# Schematic.net
KiCad netlist of a schematic drawn in Altium Designer
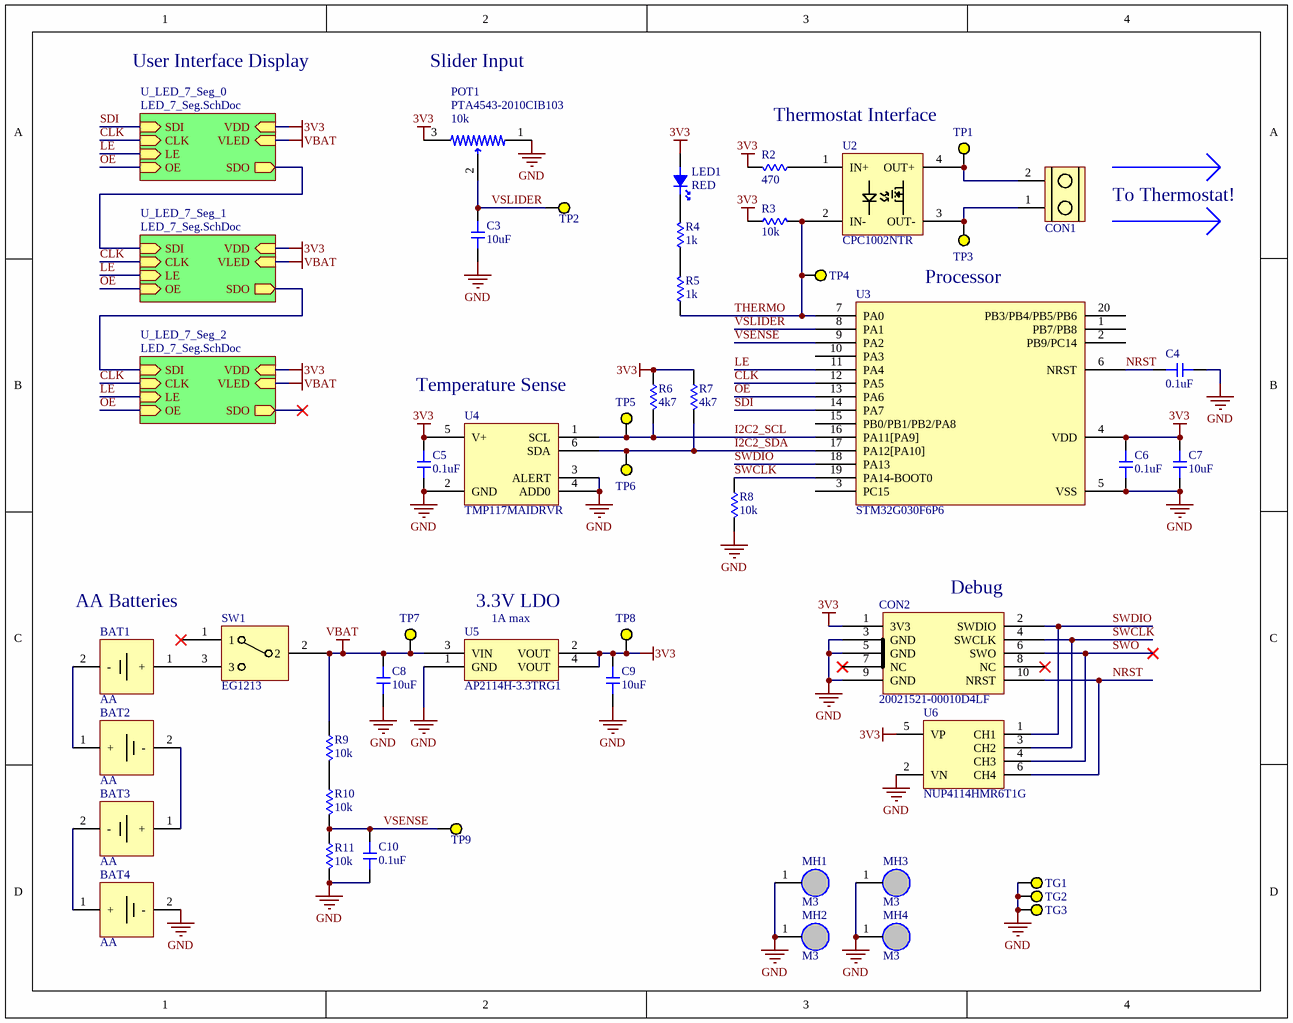
[diagram p0: Schematic.SchDoc]

(export (version "E")
  (design (tool "Eeschema 10.0.6"))
  (components
    (comp (ref "BAT1")
      (value "AA")
      (footprint "AA_BATTERY")
      (description "AA BATTERY")
      (libsource (lib "") (part "AA_BATTERY_1"))
    )
    (comp (ref "BAT2")
      (value "AA")
      (footprint "AA_BATTERY")
      (description "AA BATTERY")
      (libsource (lib "Schlib") (part "AA_BATTERY"))
    )
    (comp (ref "BAT3")
      (value "AA")
      (footprint "AA_BATTERY")
      (description "AA BATTERY")
      (libsource (lib "") (part "AA_BATTERY_1"))
    )
    (comp (ref "BAT4")
      (value "AA")
      (footprint "AA_BATTERY")
      (description "AA BATTERY")
      (libsource (lib "Schlib") (part "AA_BATTERY"))
    )
    (comp (ref "C3")
      (value "10uF")
      (footprint "PcbLib:0603-CAP")
      (description "Capacitor")
      (libsource (lib "AMDC") (part "Capacitor"))
    )
    (comp (ref "C4")
      (value "0.1uF")
      (footprint "PcbLib:0603-CAP")
      (description "Capacitor")
      (libsource (lib "AMDC") (part "Capacitor"))
    )
    (comp (ref "C5")
      (value "0.1uF")
      (footprint "PcbLib:0603-CAP")
      (description "Capacitor")
      (libsource (lib "AMDC") (part "Capacitor"))
    )
    (comp (ref "C6")
      (value "0.1uF")
      (footprint "PcbLib:0603-CAP")
      (description "Capacitor")
      (libsource (lib "AMDC") (part "Capacitor"))
    )
    (comp (ref "C7")
      (value "10uF")
      (footprint "PcbLib:0603-CAP")
      (description "Capacitor")
      (libsource (lib "AMDC") (part "Capacitor"))
    )
    (comp (ref "C8")
      (value "10uF")
      (footprint "PcbLib:0603-CAP")
      (description "Capacitor")
      (libsource (lib "AMDC") (part "Capacitor"))
    )
    (comp (ref "C9")
      (value "10uF")
      (footprint "PcbLib:0603-CAP")
      (description "Capacitor")
      (libsource (lib "AMDC") (part "Capacitor"))
    )
    (comp (ref "C10")
      (value "0.1uF")
      (footprint "PcbLib:0603-CAP")
      (description "Capacitor")
      (libsource (lib "AMDC") (part "Capacitor"))
    )
    (comp (ref "CON1")
      (value "ScrewTerminal_1x2")
      (footprint "AMDC:1935161")
      (libsource (lib "AMDC") (part "ScrewTerminal_1x2"))
    )
    (comp (ref "CON2")
      (value "20021521-00010D4LF")
      (footprint "SensorCard:20021521-00010D4LF")
      (description "CONN HEADER SMD 10POS 1.27MM")
      (libsource (lib "SensorMotherBoard") (part "20021521-00010D4LF"))
    )
    (comp (ref "LED1") (value "RED") (footprint "PcbLib:0603-LED") (libsource (lib "AMDC") (part "LED")))
    (comp (ref "MH1")
      (value "M3")
      (footprint "M3_HOLE")
      (description "M3 MOUNTING HOLE")
      (libsource (lib "Schlib") (part "M3_HOLE"))
    )
    (comp (ref "MH2")
      (value "M3")
      (footprint "M3_HOLE")
      (description "M3 MOUNTING HOLE")
      (libsource (lib "Schlib") (part "M3_HOLE"))
    )
    (comp (ref "MH3")
      (value "M3")
      (footprint "M3_HOLE")
      (description "M3 MOUNTING HOLE")
      (libsource (lib "Schlib") (part "M3_HOLE"))
    )
    (comp (ref "MH4")
      (value "M3")
      (footprint "M3_HOLE")
      (description "M3 MOUNTING HOLE")
      (libsource (lib "Schlib") (part "M3_HOLE"))
    )
    (comp (ref "POT1")
      (value "PTA4543-2010CIB103")
      (footprint "PTA4543-2010CIB103")
      (description "SLIDE POT 10K OHM 0.25W TOP 45MM")
      (fields (field (name "ALTIUM_VALUE") "10k"))
      (libsource (lib "Schlib") (part "PTA4543-2010CIB103"))
    )
    (comp (ref "R2")
      (value "470")
      (footprint "PcbLib:0603-RES")
      (fields (field (name "Comment") "Resistor"))
      (libsource (lib "*") (part "Resistor"))
    )
    (comp (ref "R3")
      (value "10k")
      (footprint "PcbLib:0603-RES")
      (fields (field (name "Comment") "Resistor"))
      (libsource (lib "*") (part "Resistor"))
    )
    (comp (ref "R4")
      (value "1k")
      (footprint "PcbLib:0603-RES")
      (fields (field (name "Comment") "Resistor"))
      (libsource (lib "*") (part "Resistor"))
    )
    (comp (ref "R5")
      (value "1k")
      (footprint "PcbLib:0603-RES")
      (fields (field (name "Comment") "Resistor"))
      (libsource (lib "*") (part "Resistor"))
    )
    (comp (ref "R6")
      (value "4k7")
      (footprint "PcbLib:0603-RES")
      (fields (field (name "Comment") "Resistor"))
      (libsource (lib "*") (part "Resistor"))
    )
    (comp (ref "R7")
      (value "4k7")
      (footprint "PcbLib:0603-RES")
      (fields (field (name "Comment") "Resistor"))
      (libsource (lib "*") (part "Resistor"))
    )
    (comp (ref "R8")
      (value "10k")
      (footprint "PcbLib:0603-RES")
      (fields (field (name "Comment") "Resistor"))
      (libsource (lib "*") (part "Resistor"))
    )
    (comp (ref "R9")
      (value "10k")
      (footprint "PcbLib:0603-RES")
      (fields (field (name "Comment") "Resistor"))
      (libsource (lib "*") (part "Resistor"))
    )
    (comp (ref "R10")
      (value "10k")
      (footprint "PcbLib:0603-RES")
      (fields (field (name "Comment") "Resistor"))
      (libsource (lib "*") (part "Resistor"))
    )
    (comp (ref "R11")
      (value "10k")
      (footprint "PcbLib:0603-RES")
      (fields (field (name "Comment") "Resistor"))
      (libsource (lib "*") (part "Resistor"))
    )
    (comp (ref "SW1")
      (value "EG1213")
      (footprint "EG1213")
      (description "SWITCH SLIDE SPDT 200MA 30V")
      (libsource (lib "Schlib") (part "EG1213"))
    )
    (comp (ref "TG1")
      (value "RCU-0C")
      (footprint "AMDC:RCU-0C")
      (description "PC TEST POINT NATURAL")
      (libsource (lib "Altium Content Vault") (part "KSTN-TP-5004"))
    )
    (comp (ref "TG2")
      (value "RCU-0C")
      (footprint "AMDC:RCU-0C")
      (description "PC TEST POINT NATURAL")
      (libsource (lib "Altium Content Vault") (part "KSTN-TP-5004"))
    )
    (comp (ref "TG3")
      (value "RCU-0C")
      (footprint "AMDC:RCU-0C")
      (description "PC TEST POINT NATURAL")
      (libsource (lib "Altium Content Vault") (part "KSTN-TP-5004"))
    )
    (comp (ref "TP1")
      (value "RCU-0C")
      (footprint "AMDC:RCU-0C")
      (description "PC TEST POINT NATURAL")
      (libsource (lib "Altium Content Vault") (part "KSTN-TP-5004"))
    )
    (comp (ref "TP2")
      (value "RCU-0C")
      (footprint "AMDC:RCU-0C")
      (description "PC TEST POINT NATURAL")
      (libsource (lib "Altium Content Vault") (part "KSTN-TP-5004"))
    )
    (comp (ref "TP3")
      (value "RCU-0C")
      (footprint "AMDC:RCU-0C")
      (description "PC TEST POINT NATURAL")
      (libsource (lib "Altium Content Vault") (part "KSTN-TP-5004"))
    )
    (comp (ref "TP4")
      (value "RCU-0C")
      (footprint "AMDC:RCU-0C")
      (description "PC TEST POINT NATURAL")
      (libsource (lib "Altium Content Vault") (part "KSTN-TP-5004"))
    )
    (comp (ref "TP5")
      (value "RCU-0C")
      (footprint "AMDC:RCU-0C")
      (description "PC TEST POINT NATURAL")
      (libsource (lib "Altium Content Vault") (part "KSTN-TP-5004"))
    )
    (comp (ref "TP6")
      (value "RCU-0C")
      (footprint "AMDC:RCU-0C")
      (description "PC TEST POINT NATURAL")
      (libsource (lib "Altium Content Vault") (part "KSTN-TP-5004"))
    )
    (comp (ref "TP7")
      (value "RCU-0C")
      (footprint "AMDC:RCU-0C")
      (description "PC TEST POINT NATURAL")
      (libsource (lib "Altium Content Vault") (part "KSTN-TP-5004"))
    )
    (comp (ref "TP8")
      (value "RCU-0C")
      (footprint "AMDC:RCU-0C")
      (description "PC TEST POINT NATURAL")
      (libsource (lib "Altium Content Vault") (part "KSTN-TP-5004"))
    )
    (comp (ref "TP9")
      (value "RCU-0C")
      (footprint "AMDC:RCU-0C")
      (description "PC TEST POINT NATURAL")
      (libsource (lib "Altium Content Vault") (part "KSTN-TP-5004"))
    )
    (comp (ref "U2")
      (value "CPC1002NTR")
      (footprint "CPC1002NTR")
      (description "SSR RELAY SPST-NO 700MA 0-60V")
      (libsource (lib "Schlib") (part "CPC1002NTR"))
    )
    (comp (ref "U3")
      (value "STM32G030F6P6")
      (footprint "TSOP65P640X120-20N")
      (description "ARM MICROCONTROLLERS - MCU")
      (libsource (lib "Schlib") (part "STM32G030F6P6"))
    )
    (comp (ref "U4")
      (value "TMP117MAIDRVR")
      (footprint "SON65P200X80_HS-7N")
      (description "TEMPERATURE SENSOR")
      (libsource (lib "Schlib") (part "TMP117MAIDRVR"))
    )
    (comp (ref "U5")
      (value "AP2114H-3.3TRG1")
      (footprint "AMDC:SOT230P700X180-4N")
      (description "IC REG LINEAR 3.3V 1A SOT223")
      (libsource (lib "AMDC") (part "AP2114H-3.3TRG1"))
    )
    (comp (ref "U6")
      (value "NUP4114HMR6T1G")
      (footprint "AMDC:TSOP95P280X110-6N")
      (description "TVS DIODE 5.5V 10V 6TSOP")
      (libsource (lib "AMDC") (part "NUP4114HMR6T1G"))
    )
  )
  (nets
    (net (code "1") (name "/CLK") (class "Default")
      (node (ref "U3") (pin "12") (pinfunction "PA5_12") (pintype "passive"))
    )
    (net (code "2") (name "/I2C2_SCL") (class "Default")
      (node (ref "R6") (pin "2") (pinfunction "2_2") (pintype "passive"))
      (node (ref "TP5") (pin "1") (pinfunction "1_1") (pintype "passive"))
      (node (ref "U3") (pin "16") (pinfunction "PA11[PA9]_16") (pintype "passive"))
      (node (ref "U4") (pin "1") (pinfunction "SCL_1") (pintype "passive"))
    )
    (net (code "3") (name "/I2C2_SDA") (class "Default")
      (node (ref "R7") (pin "2") (pinfunction "2_2") (pintype "passive"))
      (node (ref "TP6") (pin "1") (pinfunction "1_1") (pintype "passive"))
      (node (ref "U3") (pin "17") (pinfunction "PA12[PA10]_17") (pintype "passive"))
      (node (ref "U4") (pin "6") (pinfunction "SDA_6") (pintype "passive"))
    )
    (net (code "4") (name "/LE") (class "Default")
      (node (ref "U3") (pin "11") (pinfunction "PA4_11") (pintype "passive"))
    )
    (net (code "5") (name "/NRST") (class "Default")
      (node (ref "C4") (pin "2") (pinfunction "2_2") (pintype "passive"))
      (node (ref "CON2") (pin "10") (pinfunction "NRST_10") (pintype "passive"))
      (node (ref "U3") (pin "6") (pinfunction "NRST_6") (pintype "passive"))
      (node (ref "U6") (pin "6") (pinfunction "CH4_6") (pintype "passive"))
    )
    (net (code "6") (name "/OE") (class "Default")
      (node (ref "U3") (pin "13") (pinfunction "PA6_13") (pintype "passive"))
    )
    (net (code "7") (name "/SDI") (class "Default")
      (node (ref "U3") (pin "14") (pinfunction "PA7_14") (pintype "passive"))
    )
    (net (code "11") (name "/SWCLK") (class "Default")
      (node (ref "CON2") (pin "4") (pinfunction "SWCLK_4") (pintype "passive"))
      (node (ref "R8") (pin "1") (pinfunction "1_1") (pintype "passive"))
      (node (ref "U3") (pin "19") (pinfunction "PA14-BOOT0_19") (pintype "passive"))
      (node (ref "U6") (pin "3") (pinfunction "CH2_3") (pintype "passive"))
    )
    (net (code "12") (name "/SWDIO") (class "Default")
      (node (ref "CON2") (pin "2") (pinfunction "SWDIO_2") (pintype "passive"))
      (node (ref "U3") (pin "18") (pinfunction "PA13_18") (pintype "passive"))
      (node (ref "U6") (pin "1") (pinfunction "CH1_1") (pintype "passive"))
    )
    (net (code "13") (name "/SWO") (class "Default")
      (node (ref "CON2") (pin "6") (pinfunction "SWO_6") (pintype "passive"))
      (node (ref "U6") (pin "4") (pinfunction "CH3_4") (pintype "passive"))
    )
    (net (code "14") (name "/THERMO") (class "Default")
      (node (ref "R3") (pin "2") (pinfunction "2_2") (pintype "passive"))
      (node (ref "R5") (pin "1") (pinfunction "1_1") (pintype "passive"))
      (node (ref "TP4") (pin "1") (pinfunction "1_1") (pintype "passive"))
      (node (ref "U2") (pin "2") (pinfunction "IN-_2") (pintype "passive"))
      (node (ref "U3") (pin "7") (pinfunction "PA0_7") (pintype "passive"))
    )
    (net (code "15") (name "/VSENSE") (class "Default")
      (node (ref "C10") (pin "1") (pinfunction "1_1") (pintype "passive"))
      (node (ref "R10") (pin "2") (pinfunction "2_2") (pintype "passive"))
      (node (ref "R11") (pin "1") (pinfunction "1_1") (pintype "passive"))
      (node (ref "TP9") (pin "1") (pinfunction "1_1") (pintype "passive"))
      (node (ref "U3") (pin "9") (pinfunction "PA2_9") (pintype "passive"))
    )
    (net (code "16") (name "/VSLIDER") (class "Default")
      (node (ref "C3") (pin "1") (pinfunction "1_1") (pintype "passive"))
      (node (ref "POT1") (pin "2") (pinfunction "2_2") (pintype "passive"))
      (node (ref "TP2") (pin "1") (pinfunction "1_1") (pintype "passive"))
      (node (ref "U3") (pin "8") (pinfunction "PA1_8") (pintype "passive"))
    )
    (net (code "17") (name "3V3") (class "Default")
      (node (ref "C5") (pin "1") (pinfunction "1_1") (pintype "passive"))
      (node (ref "C6") (pin "1") (pinfunction "1_1") (pintype "passive"))
      (node (ref "C7") (pin "1") (pinfunction "1_1") (pintype "passive"))
      (node (ref "C9") (pin "1") (pinfunction "1_1") (pintype "passive"))
      (node (ref "CON2") (pin "1") (pinfunction "3V3_1") (pintype "passive"))
      (node (ref "LED1") (pin "A") (pinfunction "A_A") (pintype "passive"))
      (node (ref "POT1") (pin "3") (pinfunction "3_3") (pintype "passive"))
      (node (ref "R2") (pin "2") (pinfunction "2_2") (pintype "passive"))
      (node (ref "R3") (pin "1") (pinfunction "1_1") (pintype "passive"))
      (node (ref "R6") (pin "1") (pinfunction "1_1") (pintype "passive"))
      (node (ref "R7") (pin "1") (pinfunction "1_1") (pintype "passive"))
      (node (ref "TP8") (pin "1") (pinfunction "1_1") (pintype "passive"))
      (node (ref "U3") (pin "4") (pinfunction "VDD_4") (pintype "passive"))
      (node (ref "U4") (pin "5") (pinfunction "V+_5") (pintype "passive"))
      (node (ref "U5") (pin "2") (pinfunction "VOUT_2") (pintype "passive"))
      (node (ref "U5") (pin "4") (pinfunction "VOUT_4") (pintype "passive"))
      (node (ref "U6") (pin "5") (pinfunction "VP_5") (pintype "passive"))
    )
    (net (code "18") (name "GND") (class "Default")
      (node (ref "BAT4") (pin "2") (pinfunction "-_2") (pintype "passive"))
      (node (ref "C10") (pin "2") (pinfunction "2_2") (pintype "passive"))
      (node (ref "C3") (pin "2") (pinfunction "2_2") (pintype "passive"))
      (node (ref "C4") (pin "1") (pinfunction "1_1") (pintype "passive"))
      (node (ref "C5") (pin "2") (pinfunction "2_2") (pintype "passive"))
      (node (ref "C6") (pin "2") (pinfunction "2_2") (pintype "passive"))
      (node (ref "C7") (pin "2") (pinfunction "2_2") (pintype "passive"))
      (node (ref "C8") (pin "2") (pinfunction "2_2") (pintype "passive"))
      (node (ref "C9") (pin "2") (pinfunction "2_2") (pintype "passive"))
      (node (ref "CON2") (pin "3") (pinfunction "GND_3") (pintype "passive"))
      (node (ref "CON2") (pin "5") (pinfunction "GND_5") (pintype "passive"))
      (node (ref "CON2") (pin "9") (pinfunction "GND_9") (pintype "passive"))
      (node (ref "MH1") (pin "1") (pinfunction "1_1") (pintype "passive"))
      (node (ref "MH2") (pin "1") (pinfunction "1_1") (pintype "passive"))
      (node (ref "MH3") (pin "1") (pinfunction "1_1") (pintype "passive"))
      (node (ref "MH4") (pin "1") (pinfunction "1_1") (pintype "passive"))
      (node (ref "POT1") (pin "1") (pinfunction "1_1") (pintype "passive"))
      (node (ref "R11") (pin "2") (pinfunction "2_2") (pintype "passive"))
      (node (ref "R8") (pin "2") (pinfunction "2_2") (pintype "passive"))
      (node (ref "TG1") (pin "1") (pinfunction "1_1") (pintype "passive"))
      (node (ref "TG2") (pin "1") (pinfunction "1_1") (pintype "passive"))
      (node (ref "TG3") (pin "1") (pinfunction "1_1") (pintype "passive"))
      (node (ref "U3") (pin "5") (pinfunction "VSS_5") (pintype "passive"))
      (node (ref "U4") (pin "2") (pinfunction "GND_2") (pintype "passive"))
      (node (ref "U4") (pin "3") (pinfunction "ALERT_3") (pintype "passive"))
      (node (ref "U4") (pin "4") (pinfunction "ADD0_4") (pintype "passive"))
      (node (ref "U5") (pin "1") (pinfunction "GND_1") (pintype "passive"))
      (node (ref "U6") (pin "2") (pinfunction "VN_2") (pintype "passive"))
    )
    (net (code "19") (name "Net-(BAT1-+)") (class "Default")
      (node (ref "BAT1") (pin "1") (pinfunction "+_1") (pintype "passive"))
      (node (ref "SW1") (pin "3") (pinfunction "3_3") (pintype "passive"))
    )
    (net (code "20") (name "Net-(BAT1--)") (class "Default")
      (node (ref "BAT1") (pin "2") (pinfunction "-_2") (pintype "passive"))
      (node (ref "BAT2") (pin "1") (pinfunction "+_1") (pintype "passive"))
    )
    (net (code "21") (name "Net-(BAT2--)") (class "Default")
      (node (ref "BAT2") (pin "2") (pinfunction "-_2") (pintype "passive"))
      (node (ref "BAT3") (pin "1") (pinfunction "+_1") (pintype "passive"))
    )
    (net (code "22") (name "Net-(BAT3--)") (class "Default")
      (node (ref "BAT3") (pin "2") (pinfunction "-_2") (pintype "passive"))
      (node (ref "BAT4") (pin "1") (pinfunction "+_1") (pintype "passive"))
    )
    (net (code "23") (name "Net-(CON1-12)") (class "Default")
      (node (ref "CON1") (pin "1") (pinfunction "12_1") (pintype "passive"))
      (node (ref "TP3") (pin "1") (pinfunction "1_1") (pintype "passive"))
      (node (ref "U2") (pin "3") (pinfunction "OUT-_3") (pintype "passive"))
    )
    (net (code "24") (name "Net-(CON1-13)") (class "Default")
      (node (ref "CON1") (pin "2") (pinfunction "13_2") (pintype "passive"))
      (node (ref "TP1") (pin "1") (pinfunction "1_1") (pintype "passive"))
      (node (ref "U2") (pin "4") (pinfunction "OUT+_4") (pintype "passive"))
    )
    (net (code "25") (name "Net-(LED1-PadC)") (class "Default")
      (node (ref "LED1") (pin "C") (pinfunction "C_C") (pintype "passive"))
      (node (ref "R4") (pin "2") (pinfunction "2_2") (pintype "passive"))
    )
    (net (code "26") (name "Net-(R4-Pad1)") (class "Default")
      (node (ref "R4") (pin "1") (pinfunction "1_1") (pintype "passive"))
      (node (ref "R5") (pin "2") (pinfunction "2_2") (pintype "passive"))
    )
    (net (code "27") (name "Net-(R10-Pad1)") (class "Default")
      (node (ref "R10") (pin "1") (pinfunction "1_1") (pintype "passive"))
      (node (ref "R9") (pin "2") (pinfunction "2_2") (pintype "passive"))
    )
    (net (code "28") (name "Net-(U2-IN+)") (class "Default")
      (node (ref "R2") (pin "1") (pinfunction "1_1") (pintype "passive"))
      (node (ref "U2") (pin "1") (pinfunction "IN+_1") (pintype "passive"))
    )
    (net (code "29") (name "VBAT") (class "Default")
      (node (ref "C8") (pin "1") (pinfunction "1_1") (pintype "passive"))
      (node (ref "R9") (pin "1") (pinfunction "1_1") (pintype "passive"))
      (node (ref "SW1") (pin "2") (pinfunction "2_2") (pintype "passive"))
      (node (ref "TP7") (pin "1") (pinfunction "1_1") (pintype "passive"))
      (node (ref "U5") (pin "3") (pinfunction "VIN_3") (pintype "passive"))
    )
    (net (code "30") (name "unconnected-(CON2-NC-Pad7)") (class "Default")
      (node (ref "CON2") (pin "7") (pinfunction "NC_7") (pintype "passive+no_connect"))
    )
    (net (code "31") (name "unconnected-(CON2-NC-Pad8)") (class "Default")
      (node (ref "CON2") (pin "8") (pinfunction "NC_8") (pintype "passive+no_connect"))
    )
    (net (code "32") (name "unconnected-(SW1-Pad1)") (class "Default")
      (node (ref "SW1") (pin "1") (pinfunction "1_1") (pintype "passive+no_connect"))
    )
    (net (code "33") (name "unconnected-(U3-PA3-Pad10)") (class "Default")
      (node (ref "U3") (pin "10") (pinfunction "PA3_10") (pintype "passive"))
    )
    (net (code "34") (name "unconnected-(U3-PB0{slash}PB1{slash}PB2{slash}PA8-Pad15)") (class "Default")
      (node (ref "U3") (pin "15") (pinfunction "PB0/PB1/PB2/PA8_15") (pintype "passive"))
    )
    (net (code "35") (name "unconnected-(U3-PB3{slash}PB4{slash}PB5{slash}PB6-Pad20)") (class "Default")
      (node (ref "U3") (pin "20") (pinfunction "PB3/PB4/PB5/PB6_20") (pintype "passive"))
    )
    (net (code "36") (name "unconnected-(U3-PB7{slash}PB8-Pad1)") (class "Default")
      (node (ref "U3") (pin "1") (pinfunction "PB7/PB8_1") (pintype "passive"))
    )
    (net (code "37") (name "unconnected-(U3-PB9{slash}PC14-Pad2)") (class "Default")
      (node (ref "U3") (pin "2") (pinfunction "PB9/PC14_2") (pintype "passive"))
    )
    (net (code "38") (name "unconnected-(U3-PC15-Pad3)") (class "Default")
      (node (ref "U3") (pin "3") (pinfunction "PC15_3") (pintype "passive"))
    )
  )
)
